# Touch_Drum_V1.net
KiCad netlist of a schematic drawn in EAGLE
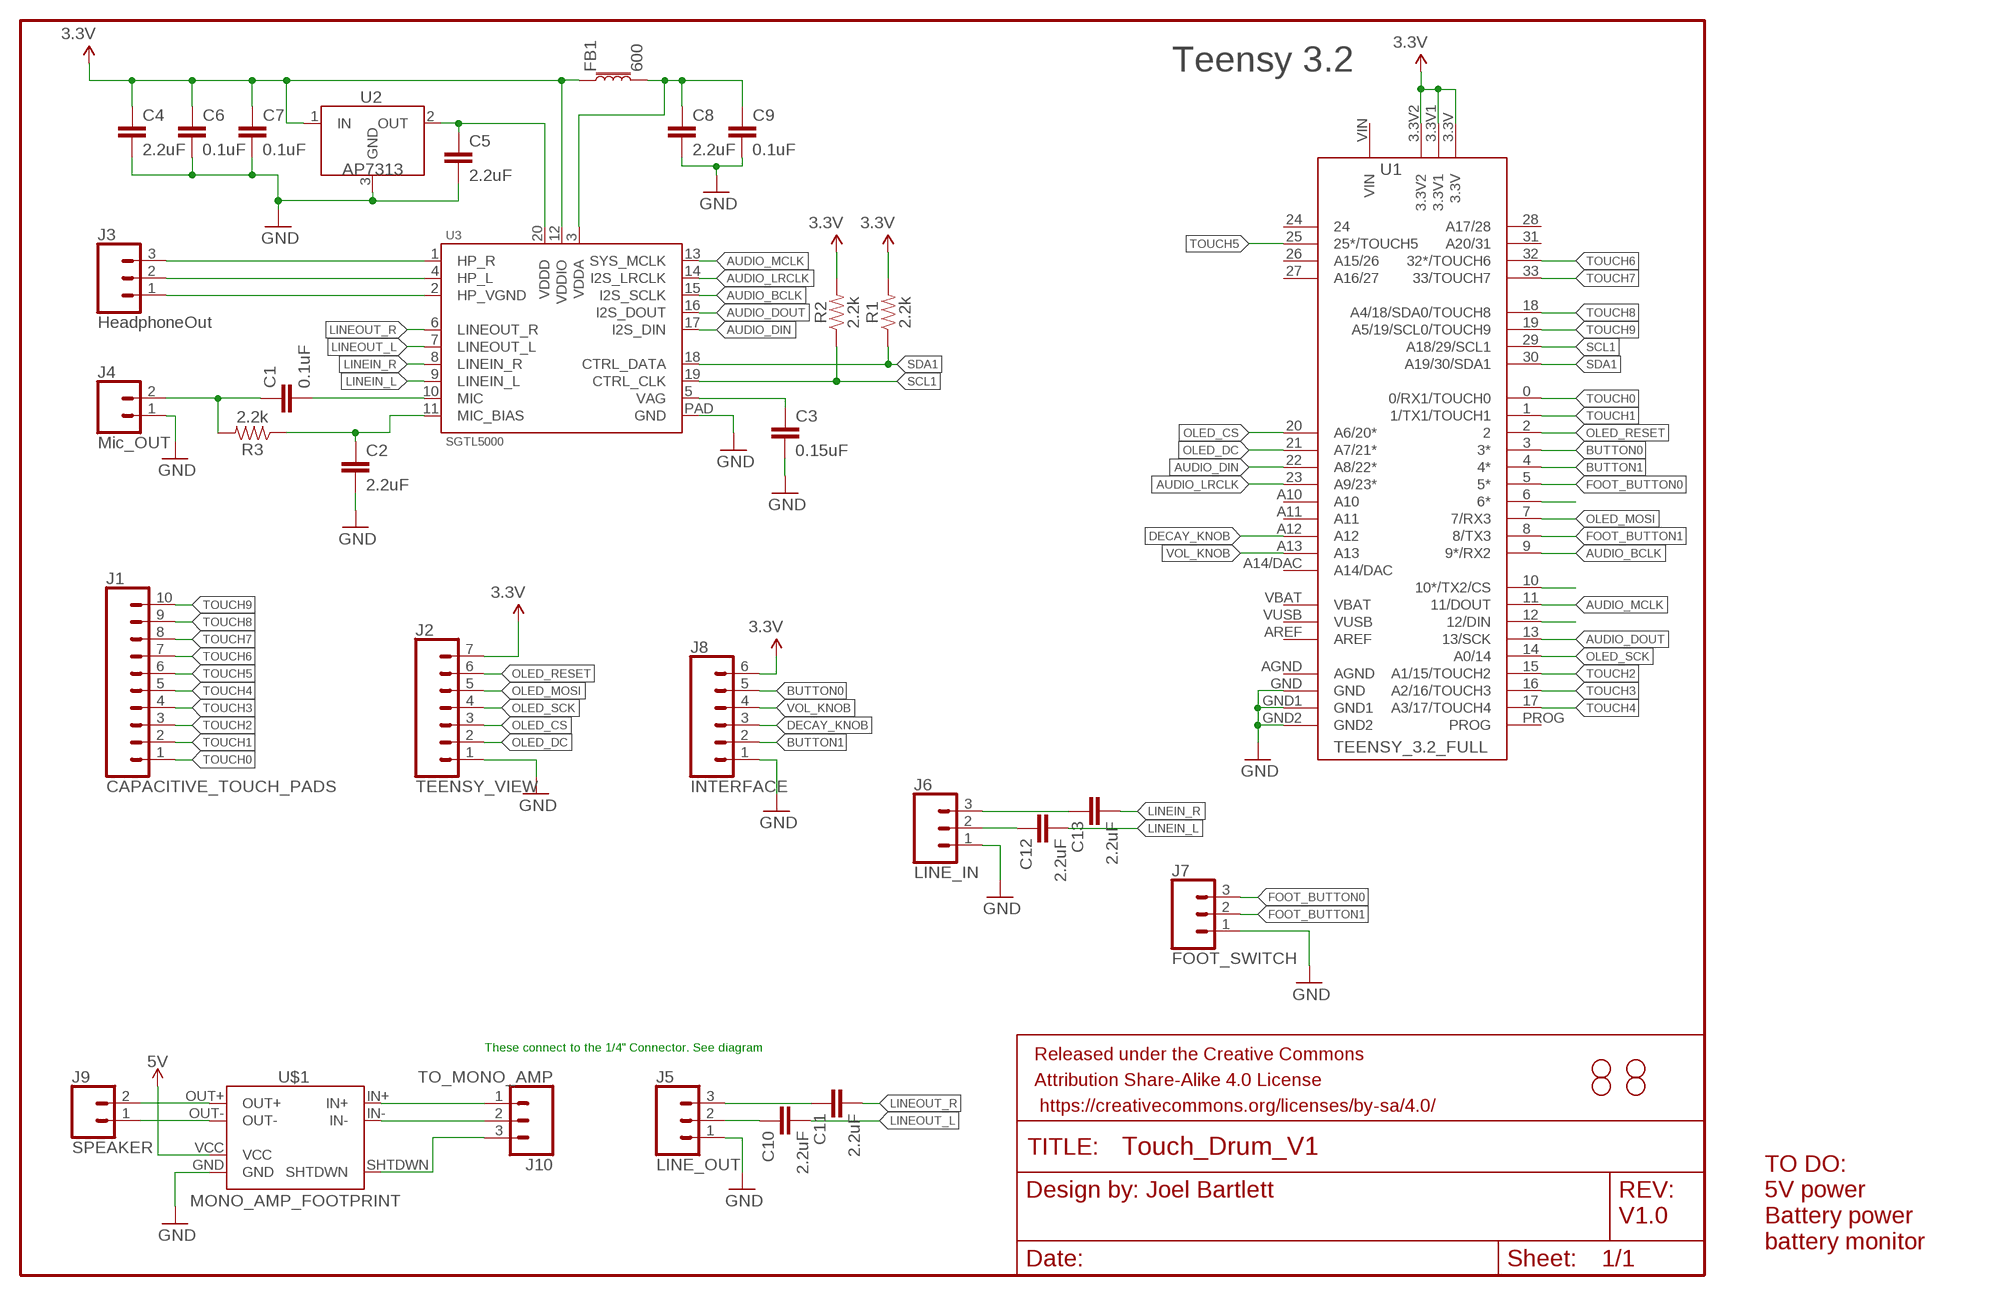
[diagram p0: schematic, sheet 1]

(export (version "E")
  (design (tool "Eeschema 10.0.6"))
  (components
    (comp (ref "C1")
      (value "0.1uF")
      (footprint "eagle-import:0603")
      (libsource (lib "eagle-import") (part "0.1UF-0603-25V-(+80/-20%)"))
    )
    (comp (ref "C2")
      (value "2.2uF")
      (footprint "eagle-import:0603")
      (libsource (lib "eagle-import") (part "2.2UF-0603-10V-20%"))
    )
    (comp (ref "C3")
      (value "0.15uF")
      (footprint "eagle-import:0603")
      (libsource (lib "eagle-import") (part "0.1UF-0603-25V-(+80/-20%)"))
    )
    (comp (ref "C4")
      (value "2.2uF")
      (footprint "eagle-import:0603")
      (libsource (lib "eagle-import") (part "2.2UF-0603-10V-20%"))
    )
    (comp (ref "C5")
      (value "2.2uF")
      (footprint "eagle-import:0603")
      (libsource (lib "eagle-import") (part "2.2UF-0603-10V-20%"))
    )
    (comp (ref "C6")
      (value "0.1uF")
      (footprint "eagle-import:0603")
      (libsource (lib "eagle-import") (part "0.1UF-0603-25V-(+80/-20%)"))
    )
    (comp (ref "C7")
      (value "0.1uF")
      (footprint "eagle-import:0603")
      (libsource (lib "eagle-import") (part "0.1UF-0603-25V-(+80/-20%)"))
    )
    (comp (ref "C8")
      (value "2.2uF")
      (footprint "eagle-import:0603")
      (libsource (lib "eagle-import") (part "2.2UF-0603-10V-20%"))
    )
    (comp (ref "C9")
      (value "0.1uF")
      (footprint "eagle-import:0603")
      (libsource (lib "eagle-import") (part "0.1UF-0603-25V-(+80/-20%)"))
    )
    (comp (ref "C10")
      (value "2.2uF")
      (footprint "eagle-import:0603")
      (libsource (lib "eagle-import") (part "2.2UF-0603-10V-20%"))
    )
    (comp (ref "C11")
      (value "2.2uF")
      (footprint "eagle-import:0603")
      (libsource (lib "eagle-import") (part "2.2UF-0603-10V-20%"))
    )
    (comp (ref "C12")
      (value "2.2uF")
      (footprint "eagle-import:0603")
      (libsource (lib "eagle-import") (part "2.2UF-0603-10V-20%"))
    )
    (comp (ref "C13")
      (value "2.2uF")
      (footprint "eagle-import:0603")
      (libsource (lib "eagle-import") (part "2.2UF-0603-10V-20%"))
    )
    (comp (ref "FB1")
      (value "600")
      (footprint "eagle-import:0603")
      (libsource (lib "eagle-import") (part "FERRITE_BEAD-0603"))
    )
    (comp (ref "FRAME1")
      (value "FRAME-LETTER")
      (footprint "eagle-import:CREATIVE_COMMONS")
      (libsource (lib "eagle-import") (part "FRAME-LETTER"))
    )
    (comp (ref "H1")
      (value "STAND-OFF")
      (footprint "eagle-import:STAND-OFF")
      (libsource (lib "eagle-import") (part "STAND-OFF"))
    )
    (comp (ref "H2")
      (value "STAND-OFF")
      (footprint "eagle-import:STAND-OFF")
      (libsource (lib "eagle-import") (part "STAND-OFF"))
    )
    (comp (ref "H3")
      (value "STAND-OFF")
      (footprint "eagle-import:STAND-OFF")
      (libsource (lib "eagle-import") (part "STAND-OFF"))
    )
    (comp (ref "H4")
      (value "STAND-OFF")
      (footprint "eagle-import:STAND-OFF")
      (libsource (lib "eagle-import") (part "STAND-OFF"))
    )
    (comp (ref "J1")
      (value "CAPACITIVE_TOUCH_PADS")
      (footprint "eagle-import:1X10_NO_SILK")
      (libsource (lib "eagle-import") (part "CONN_10NO_SILK_PTH_FEMALE"))
    )
    (comp (ref "J2")
      (value "TEENSY_VIEW")
      (footprint "eagle-import:1X07_NO_SILK")
      (libsource (lib "eagle-import") (part "CONN_07NO_SILK"))
    )
    (comp (ref "J3")
      (value "HeadphoneOut")
      (footprint "eagle-import:1X03_LONGPADS")
      (libsource (lib "eagle-import") (part "CONN_03LONGPADS"))
    )
    (comp (ref "J4")
      (value "Mic_OUT")
      (footprint "eagle-import:1X02")
      (libsource (lib "eagle-import") (part "CONN_02"))
    )
    (comp (ref "J5")
      (value "LINE_OUT")
      (footprint "eagle-import:1X03")
      (libsource (lib "eagle-import") (part "CONN_03"))
    )
    (comp (ref "J6")
      (value "LINE_IN")
      (footprint "eagle-import:1X03")
      (libsource (lib "eagle-import") (part "CONN_03"))
    )
    (comp (ref "J7")
      (value "FOOT_SWITCH")
      (footprint "eagle-import:1X03")
      (libsource (lib "eagle-import") (part "CONN_03"))
    )
    (comp (ref "J8")
      (value "INTERFACE")
      (footprint "eagle-import:1X06")
      (libsource (lib "eagle-import") (part "CONN_06SILK_FEMALE_PTH"))
    )
    (comp (ref "J9")
      (value "SPEAKER")
      (footprint "eagle-import:1X02")
      (libsource (lib "eagle-import") (part "CONN_02"))
    )
    (comp (ref "J10")
      (value "TO_MONO_AMP")
      (footprint "eagle-import:1X03")
      (libsource (lib "eagle-import") (part "CONN_03"))
    )
    (comp (ref "R1")
      (value "2.2k")
      (footprint "eagle-import:0603")
      (libsource (lib "eagle-import") (part "2.2KOHM-0603-1/10W-1%"))
    )
    (comp (ref "R2")
      (value "2.2k")
      (footprint "eagle-import:0603")
      (libsource (lib "eagle-import") (part "2.2KOHM-0603-1/10W-1%"))
    )
    (comp (ref "R3")
      (value "2.2k")
      (footprint "eagle-import:0603")
      (libsource (lib "eagle-import") (part "2.2KOHM-0603-1/10W-1%"))
    )
    (comp (ref "U$1")
      (value "MONO_AMP_FOOTPRINT")
      (footprint "eagle-import:MONO_AMP_FOOTPRINT")
      (libsource (lib "eagle-import") (part "MONO_AMP_FOOTPRINT"))
    )
    (comp (ref "U1")
      (value "TEENSY_3.2_FULL")
      (footprint "eagle-import:TEENSY_3.2_FULL")
      (libsource (lib "eagle-import") (part "TEENSY_3.2_FULL"))
    )
    (comp (ref "U2")
      (value "AP7313")
      (footprint "eagle-import:SOT23-3")
      (libsource (lib "eagle-import") (part "AP7313"))
    )
    (comp (ref "U3")
      (value "SGTL5000")
      (footprint "eagle-import:QFN20")
      (libsource (lib "eagle-import") (part "SGTL5000"))
    )
  )
  (nets
    (net (code "1") (name "3.3V") (class "Default")
      (node (ref "C4") (pin "1") (pinfunction "1_1") (pintype "passive"))
      (node (ref "C6") (pin "1") (pinfunction "1_1") (pintype "passive"))
      (node (ref "C7") (pin "1") (pinfunction "1_1") (pintype "passive"))
      (node (ref "FB1") (pin "1") (pinfunction "1_1") (pintype "passive"))
      (node (ref "J2") (pin "7") (pinfunction "7_7") (pintype "passive"))
      (node (ref "J8") (pin "6") (pinfunction "6_6") (pintype "passive"))
      (node (ref "R1") (pin "2") (pinfunction "2_2") (pintype "passive"))
      (node (ref "R2") (pin "2") (pinfunction "2_2") (pintype "passive"))
      (node (ref "U1") (pin "3.3V") (pinfunction "3.3V_3.3V") (pintype "bidirectional"))
      (node (ref "U1") (pin "3.3V1") (pinfunction "3.3V1_3.3V1") (pintype "bidirectional"))
      (node (ref "U1") (pin "3.3V2") (pinfunction "3.3V2_3.3V2") (pintype "bidirectional"))
      (node (ref "U2") (pin "1") (pinfunction "IN_1") (pintype "bidirectional"))
      (node (ref "U3") (pin "12") (pinfunction "VDDIO_12") (pintype "bidirectional"))
    )
    (net (code "2") (name "5V") (class "Default")
      (node (ref "U$1") (pin "VCC") (pinfunction "VCC_VCC") (pintype "bidirectional"))
    )
    (net (code "3") (name "AUDIO_BCLK") (class "Default")
      (node (ref "U1") (pin "9") (pinfunction "9*/RX2_9") (pintype "bidirectional"))
      (node (ref "U3") (pin "15") (pinfunction "I2S_SCLK_15") (pintype "bidirectional"))
    )
    (net (code "4") (name "AUDIO_DIN") (class "Default")
      (node (ref "U1") (pin "22") (pinfunction "A8/22*_22") (pintype "bidirectional"))
      (node (ref "U3") (pin "17") (pinfunction "I2S_DIN_17") (pintype "bidirectional"))
    )
    (net (code "5") (name "AUDIO_DOUT") (class "Default")
      (node (ref "U1") (pin "13") (pinfunction "13/SCK_13") (pintype "bidirectional"))
      (node (ref "U3") (pin "16") (pinfunction "I2S_DOUT_16") (pintype "bidirectional"))
    )
    (net (code "6") (name "AUDIO_LRCLK") (class "Default")
      (node (ref "U1") (pin "23") (pinfunction "A9/23*_23") (pintype "bidirectional"))
      (node (ref "U3") (pin "14") (pinfunction "I2S_LRCLK_14") (pintype "bidirectional"))
    )
    (net (code "7") (name "AUDIO_MCLK") (class "Default")
      (node (ref "U1") (pin "11") (pinfunction "11/DOUT_11") (pintype "bidirectional"))
      (node (ref "U3") (pin "13") (pinfunction "SYS_MCLK_13") (pintype "bidirectional"))
    )
    (net (code "8") (name "BUTTON0") (class "Default")
      (node (ref "J8") (pin "5") (pinfunction "5_5") (pintype "passive"))
      (node (ref "U1") (pin "3") (pinfunction "3*_3") (pintype "bidirectional"))
    )
    (net (code "9") (name "BUTTON1") (class "Default")
      (node (ref "J8") (pin "2") (pinfunction "2_2") (pintype "passive"))
      (node (ref "U1") (pin "4") (pinfunction "4*_4") (pintype "bidirectional"))
    )
    (net (code "10") (name "DECAY_KNOB") (class "Default")
      (node (ref "J8") (pin "3") (pinfunction "3_3") (pintype "passive"))
      (node (ref "U1") (pin "A12") (pinfunction "A12_A12") (pintype "bidirectional"))
    )
    (net (code "11") (name "FOOT_BUTTON0") (class "Default")
      (node (ref "J7") (pin "3") (pinfunction "3_3") (pintype "passive"))
      (node (ref "U1") (pin "5") (pinfunction "5*_5") (pintype "bidirectional"))
    )
    (net (code "12") (name "FOOT_BUTTON1") (class "Default")
      (node (ref "J7") (pin "2") (pinfunction "2_2") (pintype "passive"))
      (node (ref "U1") (pin "8") (pinfunction "8/TX3_8") (pintype "bidirectional"))
    )
    (net (code "13") (name "GND") (class "Default")
      (node (ref "C2") (pin "2") (pinfunction "2_2") (pintype "passive"))
      (node (ref "C3") (pin "2") (pinfunction "2_2") (pintype "passive"))
      (node (ref "C4") (pin "2") (pinfunction "2_2") (pintype "passive"))
      (node (ref "C5") (pin "2") (pinfunction "2_2") (pintype "passive"))
      (node (ref "C6") (pin "2") (pinfunction "2_2") (pintype "passive"))
      (node (ref "C7") (pin "2") (pinfunction "2_2") (pintype "passive"))
      (node (ref "C8") (pin "2") (pinfunction "2_2") (pintype "passive"))
      (node (ref "C9") (pin "2") (pinfunction "2_2") (pintype "passive"))
      (node (ref "J2") (pin "1") (pinfunction "1_1") (pintype "passive"))
      (node (ref "J4") (pin "1") (pinfunction "1_1") (pintype "passive"))
      (node (ref "J5") (pin "1") (pinfunction "1_1") (pintype "passive"))
      (node (ref "J6") (pin "1") (pinfunction "1_1") (pintype "passive"))
      (node (ref "J7") (pin "1") (pinfunction "1_1") (pintype "passive"))
      (node (ref "J8") (pin "1") (pinfunction "1_1") (pintype "passive"))
      (node (ref "U$1") (pin "GND") (pinfunction "GND_GND") (pintype "bidirectional"))
      (node (ref "U1") (pin "GND") (pinfunction "GND_GND") (pintype "bidirectional"))
      (node (ref "U1") (pin "GND1") (pinfunction "GND1_GND1") (pintype "bidirectional"))
      (node (ref "U1") (pin "GND2") (pinfunction "GND2_GND2") (pintype "bidirectional"))
      (node (ref "U2") (pin "3") (pinfunction "GND_3") (pintype "bidirectional"))
      (node (ref "U3") (pin "PAD") (pinfunction "GND_PAD") (pintype "bidirectional"))
    )
    (net (code "14") (name "LINEIN_L") (class "Default")
      (node (ref "C12") (pin "2") (pinfunction "2_2") (pintype "passive"))
      (node (ref "U3") (pin "9") (pinfunction "LINEIN_L_9") (pintype "bidirectional"))
    )
    (net (code "15") (name "LINEIN_R") (class "Default")
      (node (ref "C13") (pin "2") (pinfunction "2_2") (pintype "passive"))
      (node (ref "U3") (pin "8") (pinfunction "LINEIN_R_8") (pintype "bidirectional"))
    )
    (net (code "16") (name "LINEOUT_L") (class "Default")
      (node (ref "C10") (pin "2") (pinfunction "2_2") (pintype "passive"))
      (node (ref "U3") (pin "7") (pinfunction "LINEOUT_L_7") (pintype "bidirectional"))
    )
    (net (code "17") (name "LINEOUT_R") (class "Default")
      (node (ref "C11") (pin "2") (pinfunction "2_2") (pintype "passive"))
      (node (ref "U3") (pin "6") (pinfunction "LINEOUT_R_6") (pintype "bidirectional"))
    )
    (net (code "18") (name "Net-(C1-Pad1)") (class "Default")
      (node (ref "C1") (pin "1") (pinfunction "1_1") (pintype "passive"))
      (node (ref "J4") (pin "2") (pinfunction "2_2") (pintype "passive"))
      (node (ref "R3") (pin "2") (pinfunction "2_2") (pintype "passive"))
    )
    (net (code "19") (name "Net-(C10-Pad1)") (class "Default")
      (node (ref "C10") (pin "1") (pinfunction "1_1") (pintype "passive"))
      (node (ref "J5") (pin "2") (pinfunction "2_2") (pintype "passive"))
    )
    (net (code "20") (name "Net-(C11-Pad1)") (class "Default")
      (node (ref "C11") (pin "1") (pinfunction "1_1") (pintype "passive"))
      (node (ref "J5") (pin "3") (pinfunction "3_3") (pintype "passive"))
    )
    (net (code "21") (name "Net-(C12-Pad1)") (class "Default")
      (node (ref "C12") (pin "1") (pinfunction "1_1") (pintype "passive"))
      (node (ref "J6") (pin "2") (pinfunction "2_2") (pintype "passive"))
    )
    (net (code "22") (name "Net-(C13-Pad1)") (class "Default")
      (node (ref "C13") (pin "1") (pinfunction "1_1") (pintype "passive"))
      (node (ref "J6") (pin "3") (pinfunction "3_3") (pintype "passive"))
    )
    (net (code "23") (name "Net-(J9-Pad1)") (class "Default")
      (node (ref "J9") (pin "1") (pinfunction "1_1") (pintype "passive"))
      (node (ref "U$1") (pin "OUT-") (pinfunction "OUT-_OUT-") (pintype "bidirectional"))
    )
    (net (code "24") (name "Net-(J9-Pad2)") (class "Default")
      (node (ref "J9") (pin "2") (pinfunction "2_2") (pintype "passive"))
      (node (ref "U$1") (pin "OUT+") (pinfunction "OUT+_OUT+") (pintype "bidirectional"))
    )
    (net (code "25") (name "Net-(J10-Pad1)") (class "Default")
      (node (ref "J10") (pin "1") (pinfunction "1_1") (pintype "passive"))
      (node (ref "U$1") (pin "IN+") (pinfunction "IN+_IN+") (pintype "bidirectional"))
    )
    (net (code "26") (name "Net-(J10-Pad2)") (class "Default")
      (node (ref "J10") (pin "2") (pinfunction "2_2") (pintype "passive"))
      (node (ref "U$1") (pin "IN-") (pinfunction "IN-_IN-") (pintype "bidirectional"))
    )
    (net (code "27") (name "Net-(J10-Pad3)") (class "Default")
      (node (ref "J10") (pin "3") (pinfunction "3_3") (pintype "passive"))
      (node (ref "U$1") (pin "SHTDWN") (pinfunction "SHTDWN_SHTDWN") (pintype "bidirectional"))
    )
    (net (code "28") (name "Net-(U2-OUT)") (class "Default")
      (node (ref "C5") (pin "1") (pinfunction "1_1") (pintype "passive"))
      (node (ref "U2") (pin "2") (pinfunction "OUT_2") (pintype "bidirectional"))
      (node (ref "U3") (pin "20") (pinfunction "VDDD_20") (pintype "bidirectional"))
    )
    (net (code "29") (name "Net-(U3-HP_L)") (class "Default")
      (node (ref "J3") (pin "2") (pinfunction "2_2") (pintype "passive"))
      (node (ref "U3") (pin "4") (pinfunction "HP_L_4") (pintype "bidirectional"))
    )
    (net (code "30") (name "Net-(U3-HP_R)") (class "Default")
      (node (ref "J3") (pin "3") (pinfunction "3_3") (pintype "passive"))
      (node (ref "U3") (pin "1") (pinfunction "HP_R_1") (pintype "bidirectional"))
    )
    (net (code "31") (name "Net-(U3-HP_VGND)") (class "Default")
      (node (ref "J3") (pin "1") (pinfunction "1_1") (pintype "passive"))
      (node (ref "U3") (pin "2") (pinfunction "HP_VGND_2") (pintype "bidirectional"))
    )
    (net (code "32") (name "Net-(U3-MIC)") (class "Default")
      (node (ref "C1") (pin "2") (pinfunction "2_2") (pintype "passive"))
      (node (ref "U3") (pin "10") (pinfunction "MIC_10") (pintype "bidirectional"))
    )
    (net (code "33") (name "Net-(U3-MIC_BIAS)") (class "Default")
      (node (ref "C2") (pin "1") (pinfunction "1_1") (pintype "passive"))
      (node (ref "R3") (pin "1") (pinfunction "1_1") (pintype "passive"))
      (node (ref "U3") (pin "11") (pinfunction "MIC_BIAS_11") (pintype "bidirectional"))
    )
    (net (code "34") (name "Net-(U3-VAG)") (class "Default")
      (node (ref "C3") (pin "1") (pinfunction "1_1") (pintype "passive"))
      (node (ref "U3") (pin "5") (pinfunction "VAG_5") (pintype "bidirectional"))
    )
    (net (code "35") (name "Net-(U3-VDDA)") (class "Default")
      (node (ref "C8") (pin "1") (pinfunction "1_1") (pintype "passive"))
      (node (ref "C9") (pin "1") (pinfunction "1_1") (pintype "passive"))
      (node (ref "FB1") (pin "2") (pinfunction "2_2") (pintype "passive"))
      (node (ref "U3") (pin "3") (pinfunction "VDDA_3") (pintype "bidirectional"))
    )
    (net (code "36") (name "OLED_CS") (class "Default")
      (node (ref "J2") (pin "3") (pinfunction "3_3") (pintype "passive"))
      (node (ref "U1") (pin "20") (pinfunction "A6/20*_20") (pintype "bidirectional"))
    )
    (net (code "37") (name "OLED_DC") (class "Default")
      (node (ref "J2") (pin "2") (pinfunction "2_2") (pintype "passive"))
      (node (ref "U1") (pin "21") (pinfunction "A7/21*_21") (pintype "bidirectional"))
    )
    (net (code "38") (name "OLED_MOSI") (class "Default")
      (node (ref "J2") (pin "5") (pinfunction "5_5") (pintype "passive"))
      (node (ref "U1") (pin "7") (pinfunction "7/RX3_7") (pintype "bidirectional"))
    )
    (net (code "39") (name "OLED_RESET") (class "Default")
      (node (ref "J2") (pin "6") (pinfunction "6_6") (pintype "passive"))
      (node (ref "U1") (pin "2") (pinfunction "2_2") (pintype "bidirectional"))
    )
    (net (code "40") (name "OLED_SCK") (class "Default")
      (node (ref "J2") (pin "4") (pinfunction "4_4") (pintype "passive"))
      (node (ref "U1") (pin "14") (pinfunction "A0/14_14") (pintype "bidirectional"))
    )
    (net (code "41") (name "SCL1") (class "Default")
      (node (ref "R2") (pin "1") (pinfunction "1_1") (pintype "passive"))
      (node (ref "U1") (pin "29") (pinfunction "A18/29/SCL1_29") (pintype "bidirectional"))
      (node (ref "U3") (pin "19") (pinfunction "CTRL_CLK_19") (pintype "bidirectional"))
    )
    (net (code "42") (name "SDA1") (class "Default")
      (node (ref "R1") (pin "1") (pinfunction "1_1") (pintype "passive"))
      (node (ref "U1") (pin "30") (pinfunction "A19/30/SDA1_30") (pintype "bidirectional"))
      (node (ref "U3") (pin "18") (pinfunction "CTRL_DATA_18") (pintype "bidirectional"))
    )
    (net (code "43") (name "TOUCH0") (class "Default")
      (node (ref "J1") (pin "1") (pinfunction "1_1") (pintype "passive"))
      (node (ref "U1") (pin "0") (pinfunction "0/RX1/TOUCH0_0") (pintype "bidirectional"))
    )
    (net (code "44") (name "TOUCH1") (class "Default")
      (node (ref "J1") (pin "2") (pinfunction "2_2") (pintype "passive"))
      (node (ref "U1") (pin "1") (pinfunction "1/TX1/TOUCH1_1") (pintype "bidirectional"))
    )
    (net (code "45") (name "TOUCH2") (class "Default")
      (node (ref "J1") (pin "3") (pinfunction "3_3") (pintype "passive"))
      (node (ref "U1") (pin "15") (pinfunction "A1/15/TOUCH2_15") (pintype "bidirectional"))
    )
    (net (code "46") (name "TOUCH3") (class "Default")
      (node (ref "J1") (pin "4") (pinfunction "4_4") (pintype "passive"))
      (node (ref "U1") (pin "16") (pinfunction "A2/16/TOUCH3_16") (pintype "bidirectional"))
    )
    (net (code "47") (name "TOUCH4") (class "Default")
      (node (ref "J1") (pin "5") (pinfunction "5_5") (pintype "passive"))
      (node (ref "U1") (pin "17") (pinfunction "A3/17/TOUCH4_17") (pintype "bidirectional"))
    )
    (net (code "48") (name "TOUCH5") (class "Default")
      (node (ref "J1") (pin "6") (pinfunction "6_6") (pintype "passive"))
      (node (ref "U1") (pin "25") (pinfunction "25*/TOUCH5_25") (pintype "bidirectional"))
    )
    (net (code "49") (name "TOUCH6") (class "Default")
      (node (ref "J1") (pin "7") (pinfunction "7_7") (pintype "passive"))
      (node (ref "U1") (pin "32") (pinfunction "32*/TOUCH6_32") (pintype "bidirectional"))
    )
    (net (code "50") (name "TOUCH7") (class "Default")
      (node (ref "J1") (pin "8") (pinfunction "8_8") (pintype "passive"))
      (node (ref "U1") (pin "33") (pinfunction "33/TOUCH7_33") (pintype "bidirectional"))
    )
    (net (code "51") (name "TOUCH8") (class "Default")
      (node (ref "J1") (pin "9") (pinfunction "9_9") (pintype "passive"))
      (node (ref "U1") (pin "18") (pinfunction "A4/18/SDA0/TOUCH8_18") (pintype "bidirectional"))
    )
    (net (code "52") (name "TOUCH9") (class "Default")
      (node (ref "J1") (pin "10") (pinfunction "10_10") (pintype "passive"))
      (node (ref "U1") (pin "19") (pinfunction "A5/19/SCL0/TOUCH9_19") (pintype "bidirectional"))
    )
    (net (code "53") (name "VOL_KNOB") (class "Default")
      (node (ref "J8") (pin "4") (pinfunction "4_4") (pintype "passive"))
      (node (ref "U1") (pin "A13") (pinfunction "A13_A13") (pintype "bidirectional"))
    )
    (net (code "54") (name "unconnected-(U1-6*-Pad6)") (class "Default")
      (node (ref "U1") (pin "6") (pinfunction "6*_6") (pintype "bidirectional"))
    )
    (net (code "55") (name "unconnected-(U1-10*{slash}TX2{slash}CS-Pad10)") (class "Default")
      (node (ref "U1") (pin "10") (pinfunction "10*/TX2/CS_10") (pintype "bidirectional"))
    )
    (net (code "56") (name "unconnected-(U1-12{slash}DIN-Pad12)") (class "Default")
      (node (ref "U1") (pin "12") (pinfunction "12/DIN_12") (pintype "bidirectional"))
    )
    (net (code "57") (name "unconnected-(U1-A15{slash}26-Pad26)") (class "Default")
      (node (ref "U1") (pin "26") (pinfunction "A15/26_26") (pintype "bidirectional"))
    )
    (net (code "58") (name "unconnected-(U1-A16{slash}27-Pad27)") (class "Default")
      (node (ref "U1") (pin "27") (pinfunction "A16/27_27") (pintype "bidirectional"))
    )
    (net (code "59") (name "unconnected-(U1-A17{slash}28-Pad28)") (class "Default")
      (node (ref "U1") (pin "28") (pinfunction "A17/28_28") (pintype "bidirectional"))
    )
    (net (code "60") (name "unconnected-(U1-A20{slash}31-Pad31)") (class "Default")
      (node (ref "U1") (pin "31") (pinfunction "A20/31_31") (pintype "bidirectional"))
    )
    (net (code "61") (name "unconnected-(U1-Pad24)") (class "Default")
      (node (ref "U1") (pin "24") (pinfunction "24_24") (pintype "bidirectional"))
    )
    (net (code "62") (name "unconnected-(U1-PadA10)") (class "Default")
      (node (ref "U1") (pin "A10") (pinfunction "A10_A10") (pintype "bidirectional"))
    )
    (net (code "63") (name "unconnected-(U1-PadA11)") (class "Default")
      (node (ref "U1") (pin "A11") (pinfunction "A11_A11") (pintype "bidirectional"))
    )
    (net (code "64") (name "unconnected-(U1-PadA14{slash}DAC)") (class "Default")
      (node (ref "U1") (pin "A14/DAC") (pinfunction "A14/DAC_A14/DAC") (pintype "bidirectional"))
    )
    (net (code "65") (name "unconnected-(U1-PadAGND)") (class "Default")
      (node (ref "U1") (pin "AGND") (pinfunction "AGND_AGND") (pintype "bidirectional"))
    )
    (net (code "66") (name "unconnected-(U1-PadAREF)") (class "Default")
      (node (ref "U1") (pin "AREF") (pinfunction "AREF_AREF") (pintype "bidirectional"))
    )
    (net (code "67") (name "unconnected-(U1-PadPROG)") (class "Default")
      (node (ref "U1") (pin "PROG") (pinfunction "PROG_PROG") (pintype "bidirectional"))
    )
    (net (code "68") (name "unconnected-(U1-PadVBAT)") (class "Default")
      (node (ref "U1") (pin "VBAT") (pinfunction "VBAT_VBAT") (pintype "bidirectional"))
    )
    (net (code "69") (name "unconnected-(U1-PadVIN)") (class "Default")
      (node (ref "U1") (pin "VIN") (pinfunction "VIN_VIN") (pintype "bidirectional"))
    )
    (net (code "70") (name "unconnected-(U1-PadVUSB)") (class "Default")
      (node (ref "U1") (pin "VUSB") (pinfunction "VUSB_VUSB") (pintype "bidirectional"))
    )
  )
)
